# Single-Channel-OpAmp_V1.net
KiCad netlist of a schematic drawn in EAGLE
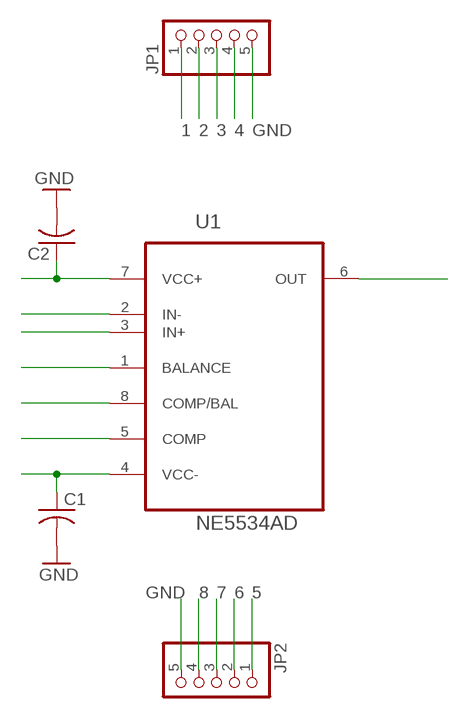
[diagram p0: schematic, sheet 1]

(export (version "E")
  (design (tool "Eeschema 10.0.6"))
  (components
    (comp (ref "C1")
      (value "C-USC0805")
      (footprint "eagle-import:C0805")
      (libsource (lib "eagle-import") (part "C-USC0805"))
    )
    (comp (ref "C2")
      (value "C-USC0805")
      (footprint "eagle-import:C0805")
      (libsource (lib "eagle-import") (part "C-USC0805"))
    )
    (comp (ref "JP1")
      (value "PINHD-1X5")
      (footprint "eagle-import:1X05")
      (libsource (lib "eagle-import") (part "PINHD-1X5"))
    )
    (comp (ref "JP2")
      (value "PINHD-1X5")
      (footprint "eagle-import:1X05")
      (libsource (lib "eagle-import") (part "PINHD-1X5"))
    )
    (comp (ref "U1")
      (value "NE5534AD")
      (footprint "eagle-import:SOIC127P600X175-8N")
      (libsource (lib "eagle-import") (part "NE5534AD"))
    )
  )
  (nets
    (net (code "1") (name "/1") (class "Default")
      (node (ref "JP1") (pin "1") (pinfunction "1_1") (pintype "passive"))
      (node (ref "U1") (pin "1") (pinfunction "BALANCE_1") (pintype "input"))
    )
    (net (code "2") (name "/2") (class "Default")
      (node (ref "JP1") (pin "2") (pinfunction "2_2") (pintype "passive"))
      (node (ref "U1") (pin "2") (pinfunction "IN-_2") (pintype "input"))
    )
    (net (code "3") (name "/3") (class "Default")
      (node (ref "JP1") (pin "3") (pinfunction "3_3") (pintype "passive"))
      (node (ref "U1") (pin "3") (pinfunction "IN+_3") (pintype "input"))
    )
    (net (code "4") (name "/4") (class "Default")
      (node (ref "C1") (pin "1") (pinfunction "1_1") (pintype "passive"))
      (node (ref "JP1") (pin "4") (pinfunction "4_4") (pintype "passive"))
      (node (ref "U1") (pin "4") (pinfunction "VCC-_4") (pintype "power_in"))
    )
    (net (code "5") (name "/5") (class "Default")
      (node (ref "JP2") (pin "1") (pinfunction "1_1") (pintype "passive"))
      (node (ref "U1") (pin "5") (pinfunction "COMP_5") (pintype "input"))
    )
    (net (code "6") (name "/6") (class "Default")
      (node (ref "JP2") (pin "2") (pinfunction "2_2") (pintype "passive"))
      (node (ref "U1") (pin "6") (pinfunction "OUT_6") (pintype "output"))
    )
    (net (code "7") (name "/7") (class "Default")
      (node (ref "C2") (pin "1") (pinfunction "1_1") (pintype "passive"))
      (node (ref "JP2") (pin "3") (pinfunction "3_3") (pintype "passive"))
      (node (ref "U1") (pin "7") (pinfunction "VCC+_7") (pintype "power_in"))
    )
    (net (code "8") (name "/8") (class "Default")
      (node (ref "JP2") (pin "4") (pinfunction "4_4") (pintype "passive"))
      (node (ref "U1") (pin "8") (pinfunction "COMP/BAL_8") (pintype "input"))
    )
    (net (code "9") (name "GND") (class "Default")
      (node (ref "C1") (pin "2") (pinfunction "2_2") (pintype "passive"))
      (node (ref "C2") (pin "2") (pinfunction "2_2") (pintype "passive"))
      (node (ref "JP1") (pin "5") (pinfunction "5_5") (pintype "passive"))
      (node (ref "JP2") (pin "5") (pinfunction "5_5") (pintype "passive"))
    )
  )
)
